# ignition.net
KiCad netlist of a schematic drawn in Altium Designer
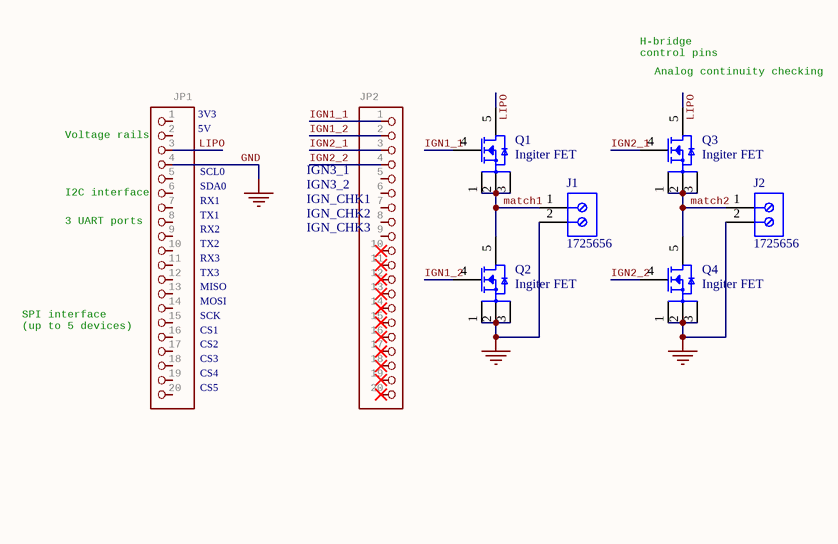
[diagram p0: ignition.SchDoc]

(export (version "E")
  (design (tool "Eeschema 10.0.6"))
  (components
    (comp (ref "J1")
      (value "1725656")
      (footprint "PHOE-1725656-2")
      (description "Male Header, Pitch 2.54 mm, 1 x 2 Position, Height 9 mm, Tail Length 3.5 mm")
      (fields (field (name "MANUFACTURER") "Phoenix Contact"))
      (libsource (lib "Altium Content Vault") (part "CN-1P-F-TB2"))
    )
    (comp (ref "J2")
      (value "1725656")
      (footprint "PHOE-1725656-2")
      (description "Male Header, Pitch 2.54 mm, 1 x 2 Position, Height 9 mm, Tail Length 3.5 mm")
      (fields (field (name "MANUFACTURER") "Phoenix Contact"))
      (libsource (lib "Altium Content Vault") (part "CN-1P-F-TB2"))
    )
    (comp (ref "JP1")
      (value "PINHD-1X20")
      (footprint "1X20")
      (description "PIN HEADER")
      (libsource (lib "adafruit") (part "PINHD-1X20"))
    )
    (comp (ref "JP2")
      (value "PINHD-1X20")
      (footprint "1X20")
      (description "PIN HEADER")
      (libsource (lib "adafruit") (part "PINHD-1X20"))
    )
    (comp (ref "Q1")
      (value "Ingiter FET")
      (footprint "PSMN5R6-60YLX")
      (description "PSMN5R6-60YL - N-channel 60 V, 5.6 mO logic level MOSFET in LFPAK56")
      (fields
        (field (name "MANUFACTURER") "Nexperia")
        (field (name "MANUFACTURER PART NUMBER") "PSMN5R6-60YLX")
      )
      (libsource (lib "Avionics_lib") (part "PSMN5R6-60YLX"))
    )
    (comp (ref "Q2")
      (value "Ingiter FET")
      (footprint "PSMN5R6-60YLX")
      (description "PSMN5R6-60YL - N-channel 60 V, 5.6 mO logic level MOSFET in LFPAK56")
      (fields
        (field (name "MANUFACTURER") "Nexperia")
        (field (name "MANUFACTURER PART NUMBER") "PSMN5R6-60YLX")
      )
      (libsource (lib "Avionics_lib") (part "PSMN5R6-60YLX"))
    )
    (comp (ref "Q3")
      (value "Ingiter FET")
      (footprint "PSMN5R6-60YLX")
      (description "PSMN5R6-60YL - N-channel 60 V, 5.6 mO logic level MOSFET in LFPAK56")
      (fields
        (field (name "MANUFACTURER") "Nexperia")
        (field (name "MANUFACTURER PART NUMBER") "PSMN5R6-60YLX")
      )
      (libsource (lib "Avionics_lib") (part "PSMN5R6-60YLX"))
    )
    (comp (ref "Q4")
      (value "Ingiter FET")
      (footprint "PSMN5R6-60YLX")
      (description "PSMN5R6-60YL - N-channel 60 V, 5.6 mO logic level MOSFET in LFPAK56")
      (fields
        (field (name "MANUFACTURER") "Nexperia")
        (field (name "MANUFACTURER PART NUMBER") "PSMN5R6-60YLX")
      )
      (libsource (lib "Avionics_lib") (part "PSMN5R6-60YLX"))
    )
  )
  (nets
    (net (code "1") (name "/IGN1_1") (class "Default")
      (node (ref "JP2") (pin "1") (pinfunction "1_1") (pintype "passive"))
      (node (ref "Q1") (pin "4") (pinfunction "4_4") (pintype "passive"))
    )
    (net (code "2") (name "/IGN1_2") (class "Default")
      (node (ref "JP2") (pin "2") (pinfunction "2_2") (pintype "passive"))
      (node (ref "Q2") (pin "4") (pinfunction "4_4") (pintype "passive"))
    )
    (net (code "3") (name "/IGN2_1") (class "Default")
      (node (ref "JP2") (pin "3") (pinfunction "3_3") (pintype "passive"))
      (node (ref "Q3") (pin "4") (pinfunction "4_4") (pintype "passive"))
    )
    (net (code "4") (name "/IGN2_2") (class "Default")
      (node (ref "JP2") (pin "4") (pinfunction "4_4") (pintype "passive"))
      (node (ref "Q4") (pin "4") (pinfunction "4_4") (pintype "passive"))
    )
    (net (code "5") (name "/LIPO") (class "Default")
      (node (ref "JP1") (pin "3") (pinfunction "3_3") (pintype "passive"))
      (node (ref "Q1") (pin "5") (pinfunction "5_5") (pintype "passive"))
      (node (ref "Q3") (pin "5") (pinfunction "5_5") (pintype "passive"))
    )
    (net (code "6") (name "/match1") (class "Default")
      (node (ref "J1") (pin "1") (pinfunction "1_1") (pintype "passive"))
      (node (ref "Q1") (pin "1") (pinfunction "1_1") (pintype "passive"))
      (node (ref "Q1") (pin "2") (pinfunction "2_2") (pintype "passive"))
      (node (ref "Q1") (pin "3") (pinfunction "3_3") (pintype "passive"))
      (node (ref "Q2") (pin "5") (pinfunction "5_5") (pintype "passive"))
    )
    (net (code "7") (name "/match2") (class "Default")
      (node (ref "J2") (pin "1") (pinfunction "1_1") (pintype "passive"))
      (node (ref "Q3") (pin "1") (pinfunction "1_1") (pintype "passive"))
      (node (ref "Q3") (pin "2") (pinfunction "2_2") (pintype "passive"))
      (node (ref "Q3") (pin "3") (pinfunction "3_3") (pintype "passive"))
      (node (ref "Q4") (pin "5") (pinfunction "5_5") (pintype "passive"))
    )
    (net (code "8") (name "GND") (class "Default")
      (node (ref "J1") (pin "2") (pinfunction "2_2") (pintype "passive"))
      (node (ref "J2") (pin "2") (pinfunction "2_2") (pintype "passive"))
      (node (ref "JP1") (pin "4") (pinfunction "4_4") (pintype "passive"))
      (node (ref "Q2") (pin "1") (pinfunction "1_1") (pintype "passive"))
      (node (ref "Q2") (pin "2") (pinfunction "2_2") (pintype "passive"))
      (node (ref "Q2") (pin "3") (pinfunction "3_3") (pintype "passive"))
      (node (ref "Q4") (pin "1") (pinfunction "1_1") (pintype "passive"))
      (node (ref "Q4") (pin "2") (pinfunction "2_2") (pintype "passive"))
      (node (ref "Q4") (pin "3") (pinfunction "3_3") (pintype "passive"))
    )
    (net (code "9") (name "unconnected-(JP1-Pad1)") (class "Default")
      (node (ref "JP1") (pin "1") (pinfunction "1_1") (pintype "passive"))
    )
    (net (code "10") (name "unconnected-(JP1-Pad2)") (class "Default")
      (node (ref "JP1") (pin "2") (pinfunction "2_2") (pintype "passive"))
    )
    (net (code "11") (name "unconnected-(JP1-Pad5)") (class "Default")
      (node (ref "JP1") (pin "5") (pinfunction "5_5") (pintype "passive"))
    )
    (net (code "12") (name "unconnected-(JP1-Pad6)") (class "Default")
      (node (ref "JP1") (pin "6") (pinfunction "6_6") (pintype "passive"))
    )
    (net (code "13") (name "unconnected-(JP1-Pad7)") (class "Default")
      (node (ref "JP1") (pin "7") (pinfunction "7_7") (pintype "passive"))
    )
    (net (code "14") (name "unconnected-(JP1-Pad8)") (class "Default")
      (node (ref "JP1") (pin "8") (pinfunction "8_8") (pintype "passive"))
    )
    (net (code "15") (name "unconnected-(JP1-Pad9)") (class "Default")
      (node (ref "JP1") (pin "9") (pinfunction "9_9") (pintype "passive"))
    )
    (net (code "16") (name "unconnected-(JP1-Pad10)") (class "Default")
      (node (ref "JP1") (pin "10") (pinfunction "10_10") (pintype "passive"))
    )
    (net (code "17") (name "unconnected-(JP1-Pad11)") (class "Default")
      (node (ref "JP1") (pin "11") (pinfunction "11_11") (pintype "passive"))
    )
    (net (code "18") (name "unconnected-(JP1-Pad12)") (class "Default")
      (node (ref "JP1") (pin "12") (pinfunction "12_12") (pintype "passive"))
    )
    (net (code "19") (name "unconnected-(JP1-Pad13)") (class "Default")
      (node (ref "JP1") (pin "13") (pinfunction "13_13") (pintype "passive"))
    )
    (net (code "20") (name "unconnected-(JP1-Pad14)") (class "Default")
      (node (ref "JP1") (pin "14") (pinfunction "14_14") (pintype "passive"))
    )
    (net (code "21") (name "unconnected-(JP1-Pad15)") (class "Default")
      (node (ref "JP1") (pin "15") (pinfunction "15_15") (pintype "passive"))
    )
    (net (code "22") (name "unconnected-(JP1-Pad16)") (class "Default")
      (node (ref "JP1") (pin "16") (pinfunction "16_16") (pintype "passive"))
    )
    (net (code "23") (name "unconnected-(JP1-Pad17)") (class "Default")
      (node (ref "JP1") (pin "17") (pinfunction "17_17") (pintype "passive"))
    )
    (net (code "24") (name "unconnected-(JP1-Pad18)") (class "Default")
      (node (ref "JP1") (pin "18") (pinfunction "18_18") (pintype "passive"))
    )
    (net (code "25") (name "unconnected-(JP1-Pad19)") (class "Default")
      (node (ref "JP1") (pin "19") (pinfunction "19_19") (pintype "passive"))
    )
    (net (code "26") (name "unconnected-(JP1-Pad20)") (class "Default")
      (node (ref "JP1") (pin "20") (pinfunction "20_20") (pintype "passive"))
    )
    (net (code "27") (name "unconnected-(JP2-Pad5)") (class "Default")
      (node (ref "JP2") (pin "5") (pinfunction "5_5") (pintype "passive"))
    )
    (net (code "28") (name "unconnected-(JP2-Pad6)") (class "Default")
      (node (ref "JP2") (pin "6") (pinfunction "6_6") (pintype "passive"))
    )
    (net (code "29") (name "unconnected-(JP2-Pad7)") (class "Default")
      (node (ref "JP2") (pin "7") (pinfunction "7_7") (pintype "passive"))
    )
    (net (code "30") (name "unconnected-(JP2-Pad8)") (class "Default")
      (node (ref "JP2") (pin "8") (pinfunction "8_8") (pintype "passive"))
    )
    (net (code "31") (name "unconnected-(JP2-Pad9)") (class "Default")
      (node (ref "JP2") (pin "9") (pinfunction "9_9") (pintype "passive"))
    )
    (net (code "32") (name "unconnected-(JP2-Pad10)") (class "Default")
      (node (ref "JP2") (pin "10") (pinfunction "10_10") (pintype "passive+no_connect"))
    )
    (net (code "33") (name "unconnected-(JP2-Pad11)") (class "Default")
      (node (ref "JP2") (pin "11") (pinfunction "11_11") (pintype "passive+no_connect"))
    )
    (net (code "34") (name "unconnected-(JP2-Pad12)") (class "Default")
      (node (ref "JP2") (pin "12") (pinfunction "12_12") (pintype "passive+no_connect"))
    )
    (net (code "35") (name "unconnected-(JP2-Pad13)") (class "Default")
      (node (ref "JP2") (pin "13") (pinfunction "13_13") (pintype "passive+no_connect"))
    )
    (net (code "36") (name "unconnected-(JP2-Pad14)") (class "Default")
      (node (ref "JP2") (pin "14") (pinfunction "14_14") (pintype "passive+no_connect"))
    )
    (net (code "37") (name "unconnected-(JP2-Pad15)") (class "Default")
      (node (ref "JP2") (pin "15") (pinfunction "15_15") (pintype "passive+no_connect"))
    )
    (net (code "38") (name "unconnected-(JP2-Pad16)") (class "Default")
      (node (ref "JP2") (pin "16") (pinfunction "16_16") (pintype "passive+no_connect"))
    )
    (net (code "39") (name "unconnected-(JP2-Pad17)") (class "Default")
      (node (ref "JP2") (pin "17") (pinfunction "17_17") (pintype "passive+no_connect"))
    )
    (net (code "40") (name "unconnected-(JP2-Pad18)") (class "Default")
      (node (ref "JP2") (pin "18") (pinfunction "18_18") (pintype "passive+no_connect"))
    )
    (net (code "41") (name "unconnected-(JP2-Pad19)") (class "Default")
      (node (ref "JP2") (pin "19") (pinfunction "19_19") (pintype "passive+no_connect"))
    )
    (net (code "42") (name "unconnected-(JP2-Pad20)") (class "Default")
      (node (ref "JP2") (pin "20") (pinfunction "20_20") (pintype "passive+no_connect"))
    )
  )
)
